# tm7_revA.net
KiCad netlist of a schematic drawn in EAGLE
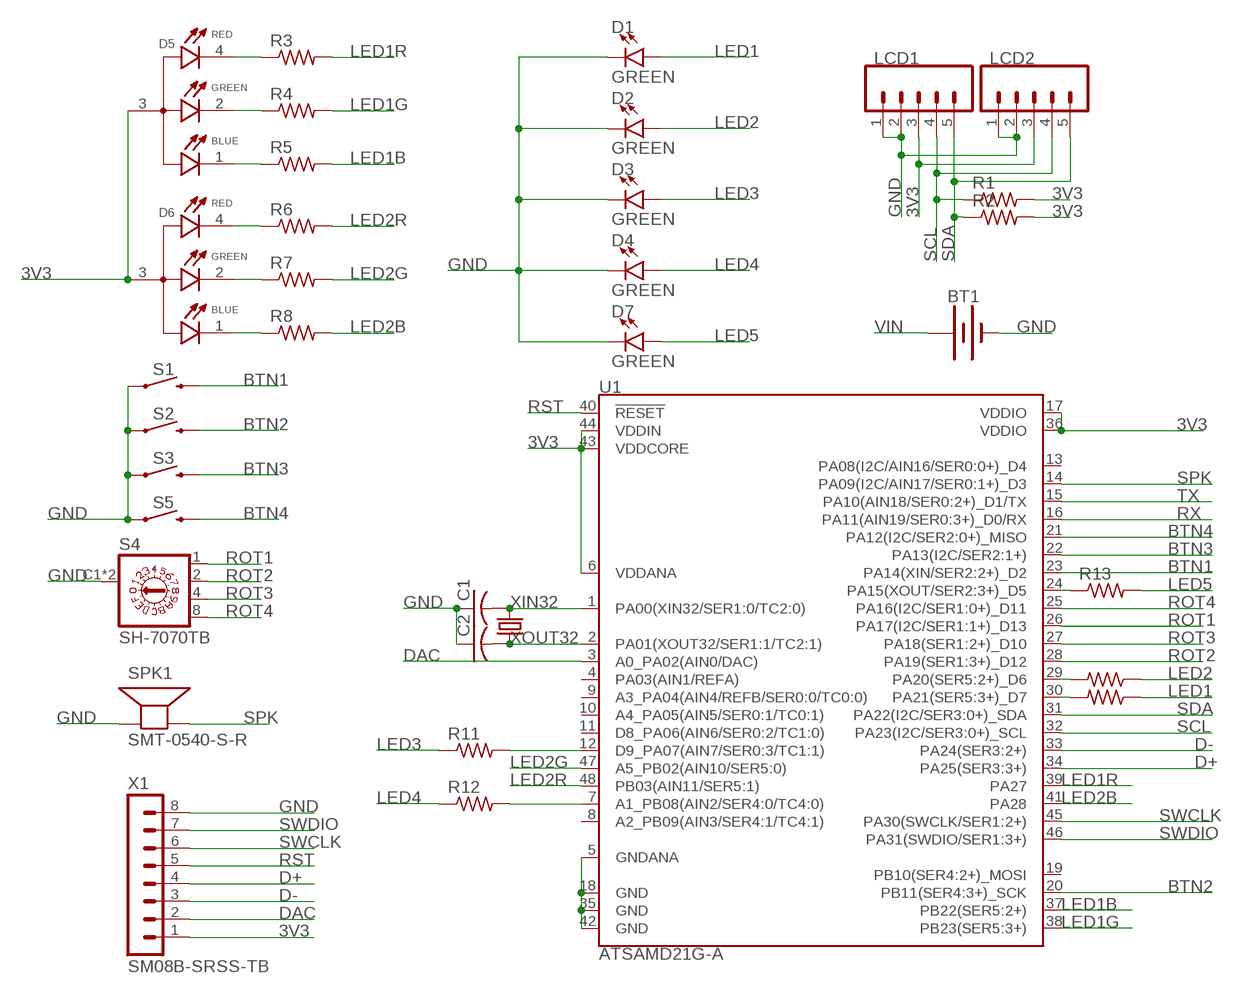
[diagram p0: schematic, sheet 1]

(export (version "E")
  (design (tool "Eeschema 10.0.6"))
  (components
    (comp (ref "BT1")
      (value "BATTERY-20MM_SMD_4LEGS_OVERPASTE_INNER")
      (footprint "eagle-import:BATTCON_20MM_4LEGS_OVERPASTE_INNER")
      (libsource (lib "eagle-import") (part "BATTERY-20MM_SMD_4LEGS_OVERPASTE_INNER"))
    )
    (comp (ref "C1")
      (value "C-USC0603")
      (footprint "eagle-import:C0603")
      (libsource (lib "eagle-import") (part "C-USC0603"))
    )
    (comp (ref "C2")
      (value "C-USC0603")
      (footprint "eagle-import:C0603")
      (libsource (lib "eagle-import") (part "C-USC0603"))
    )
    (comp (ref "D1")
      (value "GREEN")
      (footprint "eagle-import:LED-1206")
      (libsource (lib "eagle-import") (part "LED-GREEN1206"))
    )
    (comp (ref "D2")
      (value "GREEN")
      (footprint "eagle-import:LED-1206")
      (libsource (lib "eagle-import") (part "LED-GREEN1206"))
    )
    (comp (ref "D3")
      (value "GREEN")
      (footprint "eagle-import:LED-1206")
      (libsource (lib "eagle-import") (part "LED-GREEN1206"))
    )
    (comp (ref "D4")
      (value "GREEN")
      (footprint "eagle-import:LED-1206")
      (libsource (lib "eagle-import") (part "LED-GREEN1206"))
    )
    (comp (ref "D5")
      (value "EAST1616RGBA3")
      (footprint "eagle-import:LED_EAST1616RGBA3")
      (fields (field (name "MF") "Everlight Electronics"))
      (libsource (lib "eagle-import") (part "EAST1616RGBA3"))
    )
    (comp (ref "D6")
      (value "EAST1616RGBA3")
      (footprint "eagle-import:LED_EAST1616RGBA3")
      (fields (field (name "MF") "Everlight Electronics"))
      (libsource (lib "eagle-import") (part "EAST1616RGBA3"))
    )
    (comp (ref "D7")
      (value "GREEN")
      (footprint "eagle-import:LED-1206")
      (libsource (lib "eagle-import") (part "LED-GREEN1206"))
    )
    (comp (ref "LCD1")
      (value "CONN_05VERT_FEMALE_HEADER")
      (footprint "eagle-import:1X05_SMD_VERTICAL_COMBO")
      (libsource (lib "eagle-import") (part "CONN_05VERT_FEMALE_HEADER"))
    )
    (comp (ref "LCD2")
      (value "CONN_05VERT_FEMALE_HEADER")
      (footprint "eagle-import:1X05_SMD_VERTICAL_COMBO")
      (libsource (lib "eagle-import") (part "CONN_05VERT_FEMALE_HEADER"))
    )
    (comp (ref "R1")
      (value "R-US_R0603")
      (footprint "eagle-import:R0603")
      (libsource (lib "eagle-import") (part "R-US_R0603"))
    )
    (comp (ref "R2")
      (value "R-US_R0603")
      (footprint "eagle-import:R0603")
      (libsource (lib "eagle-import") (part "R-US_R0603"))
    )
    (comp (ref "R3")
      (value "R-US_R0603")
      (footprint "eagle-import:R0603")
      (libsource (lib "eagle-import") (part "R-US_R0603"))
    )
    (comp (ref "R4")
      (value "R-US_R0603")
      (footprint "eagle-import:R0603")
      (libsource (lib "eagle-import") (part "R-US_R0603"))
    )
    (comp (ref "R5")
      (value "R-US_R0603")
      (footprint "eagle-import:R0603")
      (libsource (lib "eagle-import") (part "R-US_R0603"))
    )
    (comp (ref "R6")
      (value "R-US_R0603")
      (footprint "eagle-import:R0603")
      (libsource (lib "eagle-import") (part "R-US_R0603"))
    )
    (comp (ref "R7")
      (value "R-US_R0603")
      (footprint "eagle-import:R0603")
      (libsource (lib "eagle-import") (part "R-US_R0603"))
    )
    (comp (ref "R8")
      (value "R-US_R0603")
      (footprint "eagle-import:R0603")
      (libsource (lib "eagle-import") (part "R-US_R0603"))
    )
    (comp (ref "R9")
      (value "R-US_R0603")
      (footprint "eagle-import:R0603")
      (libsource (lib "eagle-import") (part "R-US_R0603"))
    )
    (comp (ref "R10")
      (value "R-US_R0603")
      (footprint "eagle-import:R0603")
      (libsource (lib "eagle-import") (part "R-US_R0603"))
    )
    (comp (ref "R11")
      (value "R-US_R0603")
      (footprint "eagle-import:R0603")
      (libsource (lib "eagle-import") (part "R-US_R0603"))
    )
    (comp (ref "R12")
      (value "R-US_R0603")
      (footprint "eagle-import:R0603")
      (libsource (lib "eagle-import") (part "R-US_R0603"))
    )
    (comp (ref "R13")
      (value "R-US_R0603")
      (footprint "eagle-import:R0603")
      (libsource (lib "eagle-import") (part "R-US_R0603"))
    )
    (comp (ref "S1")
      (value "MOMENTARY-SWITCH-SPST-SMD-6.0X3.5MM")
      (footprint "eagle-import:TACTILE_SWITCH_SMD_6.0X3.5MM")
      (libsource (lib "eagle-import") (part "MOMENTARY-SWITCH-SPST-SMD-6.0X3.5MM"))
    )
    (comp (ref "S2")
      (value "MOMENTARY-SWITCH-SPST-SMD-6.0X3.5MM")
      (footprint "eagle-import:TACTILE_SWITCH_SMD_6.0X3.5MM")
      (libsource (lib "eagle-import") (part "MOMENTARY-SWITCH-SPST-SMD-6.0X3.5MM"))
    )
    (comp (ref "S3")
      (value "MOMENTARY-SWITCH-SPST-SMD-6.0X3.5MM")
      (footprint "eagle-import:TACTILE_SWITCH_SMD_6.0X3.5MM")
      (libsource (lib "eagle-import") (part "MOMENTARY-SWITCH-SPST-SMD-6.0X3.5MM"))
    )
    (comp (ref "S4")
      (value "SH-7070TB")
      (footprint "eagle-import:SH-7070B")
      (fields (field (name "MF") "Nidec Copal"))
      (libsource (lib "eagle-import") (part "SH-7070TB"))
    )
    (comp (ref "S5")
      (value "MOMENTARY-SWITCH-SPST-SMD-6.0X3.5MM")
      (footprint "eagle-import:TACTILE_SWITCH_SMD_6.0X3.5MM")
      (libsource (lib "eagle-import") (part "MOMENTARY-SWITCH-SPST-SMD-6.0X3.5MM"))
    )
    (comp (ref "SPK1")
      (value "SMT-0540-S-R")
      (footprint "eagle-import:SMT-0540-S-R")
      (fields (field (name "MF") "PUI"))
      (libsource (lib "eagle-import") (part "SMT-0540-S-R"))
    )
    (comp (ref "U1")
      (value "ATSAMD21G-A")
      (footprint "eagle-import:TQFP-48")
      (libsource (lib "eagle-import") (part "ATSAMD21G-A"))
    )
    (comp (ref "X1")
      (value "SM08B-SRSS-TB")
      (footprint "eagle-import:SM08B-SRSS-TB")
      (libsource (lib "eagle-import") (part "SM08B-SRSS-TB"))
    )
    (comp (ref "Y1")
      (value "32.768kHz")
      (footprint "eagle-import:CRYSTAL-SMD-3.2X1.5MM")
      (libsource (lib "eagle-import") (part "CRYSTAL-32.768KHZSMD-3.2X1.5"))
    )
  )
  (nets
    (net (code "1") (name "/3V3") (class "Default")
      (node (ref "D5") (pin "3") (pinfunction "A_3") (pintype "passive"))
      (node (ref "D6") (pin "3") (pinfunction "A_3") (pintype "passive"))
      (node (ref "LCD1") (pin "3") (pinfunction "3_3") (pintype "passive"))
      (node (ref "LCD2") (pin "3") (pinfunction "3_3") (pintype "passive"))
      (node (ref "R1") (pin "2") (pinfunction "2_2") (pintype "passive"))
      (node (ref "R2") (pin "2") (pinfunction "2_2") (pintype "passive"))
      (node (ref "U1") (pin "17") (pinfunction "VDDIO_17") (pintype "bidirectional"))
      (node (ref "U1") (pin "36") (pinfunction "VDDIO_36") (pintype "bidirectional"))
      (node (ref "U1") (pin "43") (pinfunction "VDDCORE_43") (pintype "bidirectional"))
      (node (ref "U1") (pin "44") (pinfunction "VDDIN_44") (pintype "bidirectional"))
      (node (ref "U1") (pin "6") (pinfunction "VDDANA_6") (pintype "bidirectional"))
      (node (ref "X1") (pin "1") (pinfunction "1_1") (pintype "passive"))
    )
    (net (code "2") (name "/BTN1") (class "Default")
      (node (ref "S1") (pin "2") (pinfunction "2_2") (pintype "passive"))
      (node (ref "U1") (pin "23") (pinfunction "PA14(XIN/SER2:2+)_D2_23") (pintype "bidirectional"))
    )
    (net (code "3") (name "/BTN2") (class "Default")
      (node (ref "S2") (pin "2") (pinfunction "2_2") (pintype "passive"))
      (node (ref "U1") (pin "20") (pinfunction "PB11(SER4:3+)_SCK_20") (pintype "bidirectional"))
    )
    (net (code "4") (name "/BTN3") (class "Default")
      (node (ref "S3") (pin "2") (pinfunction "2_2") (pintype "passive"))
      (node (ref "U1") (pin "22") (pinfunction "PA13(I2C/SER2:1+)_22") (pintype "bidirectional"))
    )
    (net (code "5") (name "/BTN4") (class "Default")
      (node (ref "S5") (pin "2") (pinfunction "2_2") (pintype "passive"))
      (node (ref "U1") (pin "21") (pinfunction "PA12(I2C/SER2:0+)_MISO_21") (pintype "bidirectional"))
    )
    (net (code "6") (name "/D+") (class "Default")
      (node (ref "U1") (pin "34") (pinfunction "PA25(SER3:3+)_34") (pintype "bidirectional"))
      (node (ref "X1") (pin "4") (pinfunction "4_4") (pintype "passive"))
    )
    (net (code "7") (name "/D-") (class "Default")
      (node (ref "U1") (pin "33") (pinfunction "PA24(SER3:2+)_33") (pintype "bidirectional"))
      (node (ref "X1") (pin "3") (pinfunction "3_3") (pintype "passive"))
    )
    (net (code "8") (name "/DAC") (class "Default")
      (node (ref "U1") (pin "3") (pinfunction "A0_PA02(AIN0/DAC)_3") (pintype "bidirectional"))
      (node (ref "X1") (pin "2") (pinfunction "2_2") (pintype "passive"))
    )
    (net (code "9") (name "/GND") (class "Default")
      (node (ref "BT1") (pin "2") (pinfunction "-_2") (pintype "power_in"))
      (node (ref "C1") (pin "1") (pinfunction "1_1") (pintype "passive"))
      (node (ref "C2") (pin "1") (pinfunction "1_1") (pintype "passive"))
      (node (ref "D1") (pin "C") (pinfunction "C_C") (pintype "passive"))
      (node (ref "D2") (pin "C") (pinfunction "C_C") (pintype "passive"))
      (node (ref "D3") (pin "C") (pinfunction "C_C") (pintype "passive"))
      (node (ref "D4") (pin "C") (pinfunction "C_C") (pintype "passive"))
      (node (ref "D7") (pin "C") (pinfunction "C_C") (pintype "passive"))
      (node (ref "LCD1") (pin "1") (pinfunction "1_1") (pintype "passive"))
      (node (ref "LCD1") (pin "2") (pinfunction "2_2") (pintype "passive"))
      (node (ref "LCD2") (pin "1") (pinfunction "1_1") (pintype "passive"))
      (node (ref "LCD2") (pin "2") (pinfunction "2_2") (pintype "passive"))
      (node (ref "S1") (pin "1") (pinfunction "1_1") (pintype "passive"))
      (node (ref "S2") (pin "1") (pinfunction "1_1") (pintype "passive"))
      (node (ref "S3") (pin "1") (pinfunction "1_1") (pintype "passive"))
      (node (ref "S4") (pin "C1") (pinfunction "C_C1") (pintype "passive"))
      (node (ref "S4") (pin "C2") (pinfunction "C_C2") (pintype "passive"))
      (node (ref "S5") (pin "1") (pinfunction "1_1") (pintype "passive"))
      (node (ref "SPK1") (pin "-") (pinfunction "+_-") (pintype "passive"))
      (node (ref "U1") (pin "18") (pinfunction "GND_18") (pintype "bidirectional"))
      (node (ref "U1") (pin "35") (pinfunction "GND_35") (pintype "bidirectional"))
      (node (ref "U1") (pin "42") (pinfunction "GND_42") (pintype "bidirectional"))
      (node (ref "U1") (pin "5") (pinfunction "GNDANA_5") (pintype "bidirectional"))
      (node (ref "X1") (pin "8") (pinfunction "8_8") (pintype "passive"))
    )
    (net (code "10") (name "/LED1") (class "Default")
      (node (ref "D1") (pin "A") (pinfunction "A_A") (pintype "passive"))
      (node (ref "R9") (pin "1") (pinfunction "1_1") (pintype "passive"))
    )
    (net (code "11") (name "/LED1B") (class "Default")
      (node (ref "R5") (pin "2") (pinfunction "2_2") (pintype "passive"))
      (node (ref "U1") (pin "37") (pinfunction "PB22(SER5:2+)_37") (pintype "bidirectional"))
    )
    (net (code "12") (name "/LED1G") (class "Default")
      (node (ref "R4") (pin "2") (pinfunction "2_2") (pintype "passive"))
      (node (ref "U1") (pin "38") (pinfunction "PB23(SER5:3+)_38") (pintype "bidirectional"))
    )
    (net (code "13") (name "/LED1R") (class "Default")
      (node (ref "R3") (pin "2") (pinfunction "2_2") (pintype "passive"))
      (node (ref "U1") (pin "39") (pinfunction "PA27_39") (pintype "bidirectional"))
    )
    (net (code "14") (name "/LED2") (class "Default")
      (node (ref "D2") (pin "A") (pinfunction "A_A") (pintype "passive"))
      (node (ref "R10") (pin "1") (pinfunction "1_1") (pintype "passive"))
    )
    (net (code "15") (name "/LED2B") (class "Default")
      (node (ref "R8") (pin "2") (pinfunction "2_2") (pintype "passive"))
      (node (ref "U1") (pin "41") (pinfunction "PA28_41") (pintype "bidirectional"))
    )
    (net (code "16") (name "/LED2G") (class "Default")
      (node (ref "R7") (pin "2") (pinfunction "2_2") (pintype "passive"))
      (node (ref "U1") (pin "47") (pinfunction "A5_PB02(AIN10/SER5:0)_47") (pintype "bidirectional"))
    )
    (net (code "17") (name "/LED2R") (class "Default")
      (node (ref "R6") (pin "2") (pinfunction "2_2") (pintype "passive"))
      (node (ref "U1") (pin "48") (pinfunction "PB03(AIN11/SER5:1)_48") (pintype "bidirectional"))
    )
    (net (code "18") (name "/LED3") (class "Default")
      (node (ref "D3") (pin "A") (pinfunction "A_A") (pintype "passive"))
      (node (ref "R11") (pin "1") (pinfunction "1_1") (pintype "passive"))
    )
    (net (code "19") (name "/LED4") (class "Default")
      (node (ref "D4") (pin "A") (pinfunction "A_A") (pintype "passive"))
      (node (ref "R12") (pin "1") (pinfunction "1_1") (pintype "passive"))
    )
    (net (code "20") (name "/LED5") (class "Default")
      (node (ref "D7") (pin "A") (pinfunction "A_A") (pintype "passive"))
      (node (ref "R13") (pin "2") (pinfunction "2_2") (pintype "passive"))
    )
    (net (code "21") (name "/ROT1") (class "Default")
      (node (ref "S4") (pin "1") (pinfunction "1_1") (pintype "passive"))
      (node (ref "U1") (pin "26") (pinfunction "PA17(I2C/SER1:1+)_D13_26") (pintype "bidirectional"))
    )
    (net (code "22") (name "/ROT2") (class "Default")
      (node (ref "S4") (pin "2") (pinfunction "2_2") (pintype "passive"))
      (node (ref "U1") (pin "28") (pinfunction "PA19(SER1:3+)_D12_28") (pintype "bidirectional"))
    )
    (net (code "23") (name "/ROT3") (class "Default")
      (node (ref "S4") (pin "4") (pinfunction "4_4") (pintype "passive"))
      (node (ref "U1") (pin "27") (pinfunction "PA18(SER1:2+)_D10_27") (pintype "bidirectional"))
    )
    (net (code "24") (name "/ROT4") (class "Default")
      (node (ref "S4") (pin "8") (pinfunction "8_8") (pintype "passive"))
      (node (ref "U1") (pin "25") (pinfunction "PA16(I2C/SER1:0+)_D11_25") (pintype "bidirectional"))
    )
    (net (code "25") (name "/RST") (class "Default")
      (node (ref "U1") (pin "40") (pinfunction "~{RESET}_40") (pintype "bidirectional"))
      (node (ref "X1") (pin "5") (pinfunction "5_5") (pintype "passive"))
    )
    (net (code "26") (name "/RX") (class "Default")
      (node (ref "U1") (pin "16") (pinfunction "PA11(AIN19/SER0:3+)_D0/RX_16") (pintype "bidirectional"))
    )
    (net (code "27") (name "/SCL") (class "Default")
      (node (ref "LCD1") (pin "4") (pinfunction "4_4") (pintype "passive"))
      (node (ref "LCD2") (pin "4") (pinfunction "4_4") (pintype "passive"))
      (node (ref "R1") (pin "1") (pinfunction "1_1") (pintype "passive"))
      (node (ref "U1") (pin "32") (pinfunction "PA23(I2C/SER3:0+)_SCL_32") (pintype "bidirectional"))
    )
    (net (code "28") (name "/SDA") (class "Default")
      (node (ref "LCD1") (pin "5") (pinfunction "5_5") (pintype "passive"))
      (node (ref "LCD2") (pin "5") (pinfunction "5_5") (pintype "passive"))
      (node (ref "R2") (pin "1") (pinfunction "1_1") (pintype "passive"))
      (node (ref "U1") (pin "31") (pinfunction "PA22(I2C/SER3:0+)_SDA_31") (pintype "bidirectional"))
    )
    (net (code "29") (name "/SPK") (class "Default")
      (node (ref "SPK1") (pin "+") (pinfunction "-_+") (pintype "passive"))
      (node (ref "U1") (pin "14") (pinfunction "PA09(I2C/AIN17/SER0:1+)_D3_14") (pintype "bidirectional"))
    )
    (net (code "30") (name "/SWCLK") (class "Default")
      (node (ref "U1") (pin "45") (pinfunction "PA30(SWCLK/SER1:2+)_45") (pintype "bidirectional"))
      (node (ref "X1") (pin "6") (pinfunction "6_6") (pintype "passive"))
    )
    (net (code "31") (name "/SWDIO") (class "Default")
      (node (ref "U1") (pin "46") (pinfunction "PA31(SWDIO/SER1:3+)_46") (pintype "bidirectional"))
      (node (ref "X1") (pin "7") (pinfunction "7_7") (pintype "passive"))
    )
    (net (code "32") (name "/TX") (class "Default")
      (node (ref "U1") (pin "15") (pinfunction "PA10(AIN18/SER0:2+)_D1/TX_15") (pintype "bidirectional"))
    )
    (net (code "33") (name "/VIN") (class "Default")
      (node (ref "BT1") (pin "1") (pinfunction "+_1") (pintype "power_in"))
    )
    (net (code "34") (name "/XIN32") (class "Default")
      (node (ref "C1") (pin "2") (pinfunction "2_2") (pintype "passive"))
      (node (ref "U1") (pin "1") (pinfunction "PA00(XIN32/SER1:0/TC2:0)_1") (pintype "bidirectional"))
      (node (ref "Y1") (pin "P$2") (pinfunction "2_P$2") (pintype "passive"))
    )
    (net (code "35") (name "/XOUT32") (class "Default")
      (node (ref "C2") (pin "2") (pinfunction "2_2") (pintype "passive"))
      (node (ref "U1") (pin "2") (pinfunction "PA01(XOUT32/SER1:1/TC2:1)_2") (pintype "bidirectional"))
      (node (ref "Y1") (pin "P$1") (pinfunction "1_P$1") (pintype "passive"))
    )
    (net (code "36") (name "Net-(D5-B_C)") (class "Default")
      (node (ref "D5") (pin "1") (pinfunction "B_C_1") (pintype "passive"))
      (node (ref "R5") (pin "1") (pinfunction "1_1") (pintype "passive"))
    )
    (net (code "37") (name "Net-(D5-G_C)") (class "Default")
      (node (ref "D5") (pin "2") (pinfunction "G_C_2") (pintype "passive"))
      (node (ref "R4") (pin "1") (pinfunction "1_1") (pintype "passive"))
    )
    (net (code "38") (name "Net-(D5-R_C)") (class "Default")
      (node (ref "D5") (pin "4") (pinfunction "R_C_4") (pintype "passive"))
      (node (ref "R3") (pin "1") (pinfunction "1_1") (pintype "passive"))
    )
    (net (code "39") (name "Net-(D6-B_C)") (class "Default")
      (node (ref "D6") (pin "1") (pinfunction "B_C_1") (pintype "passive"))
      (node (ref "R8") (pin "1") (pinfunction "1_1") (pintype "passive"))
    )
    (net (code "40") (name "Net-(D6-G_C)") (class "Default")
      (node (ref "D6") (pin "2") (pinfunction "G_C_2") (pintype "passive"))
      (node (ref "R7") (pin "1") (pinfunction "1_1") (pintype "passive"))
    )
    (net (code "41") (name "Net-(D6-R_C)") (class "Default")
      (node (ref "D6") (pin "4") (pinfunction "R_C_4") (pintype "passive"))
      (node (ref "R6") (pin "1") (pinfunction "1_1") (pintype "passive"))
    )
    (net (code "42") (name "Net-(U1-A1_PB08(AIN2{slash}SER4:0{slash}TC4:0))") (class "Default")
      (node (ref "R12") (pin "2") (pinfunction "2_2") (pintype "passive"))
      (node (ref "U1") (pin "7") (pinfunction "A1_PB08(AIN2/SER4:0/TC4:0)_7") (pintype "bidirectional"))
    )
    (net (code "43") (name "Net-(U1-D9_PA07(AIN7{slash}SER0:3{slash}TC1:1))") (class "Default")
      (node (ref "R11") (pin "2") (pinfunction "2_2") (pintype "passive"))
      (node (ref "U1") (pin "12") (pinfunction "D9_PA07(AIN7/SER0:3/TC1:1)_12") (pintype "bidirectional"))
    )
    (net (code "44") (name "Net-(U1-PA15(XOUT{slash}SER2:3+)_D5)") (class "Default")
      (node (ref "R13") (pin "1") (pinfunction "1_1") (pintype "passive"))
      (node (ref "U1") (pin "24") (pinfunction "PA15(XOUT/SER2:3+)_D5_24") (pintype "bidirectional"))
    )
    (net (code "45") (name "Net-(U1-PA20(SER5:2+)_D6)") (class "Default")
      (node (ref "R10") (pin "2") (pinfunction "2_2") (pintype "passive"))
      (node (ref "U1") (pin "29") (pinfunction "PA20(SER5:2+)_D6_29") (pintype "bidirectional"))
    )
    (net (code "46") (name "Net-(U1-PA21(SER5:3+)_D7)") (class "Default")
      (node (ref "R9") (pin "2") (pinfunction "2_2") (pintype "passive"))
      (node (ref "U1") (pin "30") (pinfunction "PA21(SER5:3+)_D7_30") (pintype "bidirectional"))
    )
    (net (code "47") (name "unconnected-(U1-A2_PB09(AIN3{slash}SER4:1{slash}TC4:1)-Pad8)") (class "Default")
      (node (ref "U1") (pin "8") (pinfunction "A2_PB09(AIN3/SER4:1/TC4:1)_8") (pintype "bidirectional"))
    )
    (net (code "48") (name "unconnected-(U1-A3_PA04(AIN4{slash}REFB{slash}SER0:0{slash}TC0:0)-Pad9)") (class "Default")
      (node (ref "U1") (pin "9") (pinfunction "A3_PA04(AIN4/REFB/SER0:0/TC0:0)_9") (pintype "bidirectional"))
    )
    (net (code "49") (name "unconnected-(U1-A4_PA05(AIN5{slash}SER0:1{slash}TC0:1)-Pad10)") (class "Default")
      (node (ref "U1") (pin "10") (pinfunction "A4_PA05(AIN5/SER0:1/TC0:1)_10") (pintype "bidirectional"))
    )
    (net (code "50") (name "unconnected-(U1-D8_PA06(AIN6{slash}SER0:2{slash}TC1:0)-Pad11)") (class "Default")
      (node (ref "U1") (pin "11") (pinfunction "D8_PA06(AIN6/SER0:2/TC1:0)_11") (pintype "bidirectional"))
    )
    (net (code "51") (name "unconnected-(U1-PA03(AIN1{slash}REFA)-Pad4)") (class "Default")
      (node (ref "U1") (pin "4") (pinfunction "PA03(AIN1/REFA)_4") (pintype "bidirectional"))
    )
    (net (code "52") (name "unconnected-(U1-PA08(I2C{slash}AIN16{slash}SER0:0+)_D4-Pad13)") (class "Default")
      (node (ref "U1") (pin "13") (pinfunction "PA08(I2C/AIN16/SER0:0+)_D4_13") (pintype "bidirectional"))
    )
    (net (code "53") (name "unconnected-(U1-PB10(SER4:2+)_MOSI-Pad19)") (class "Default")
      (node (ref "U1") (pin "19") (pinfunction "PB10(SER4:2+)_MOSI_19") (pintype "bidirectional"))
    )
  )
)
